# Coco2Composite.net
KiCad netlist of a schematic drawn in EAGLE
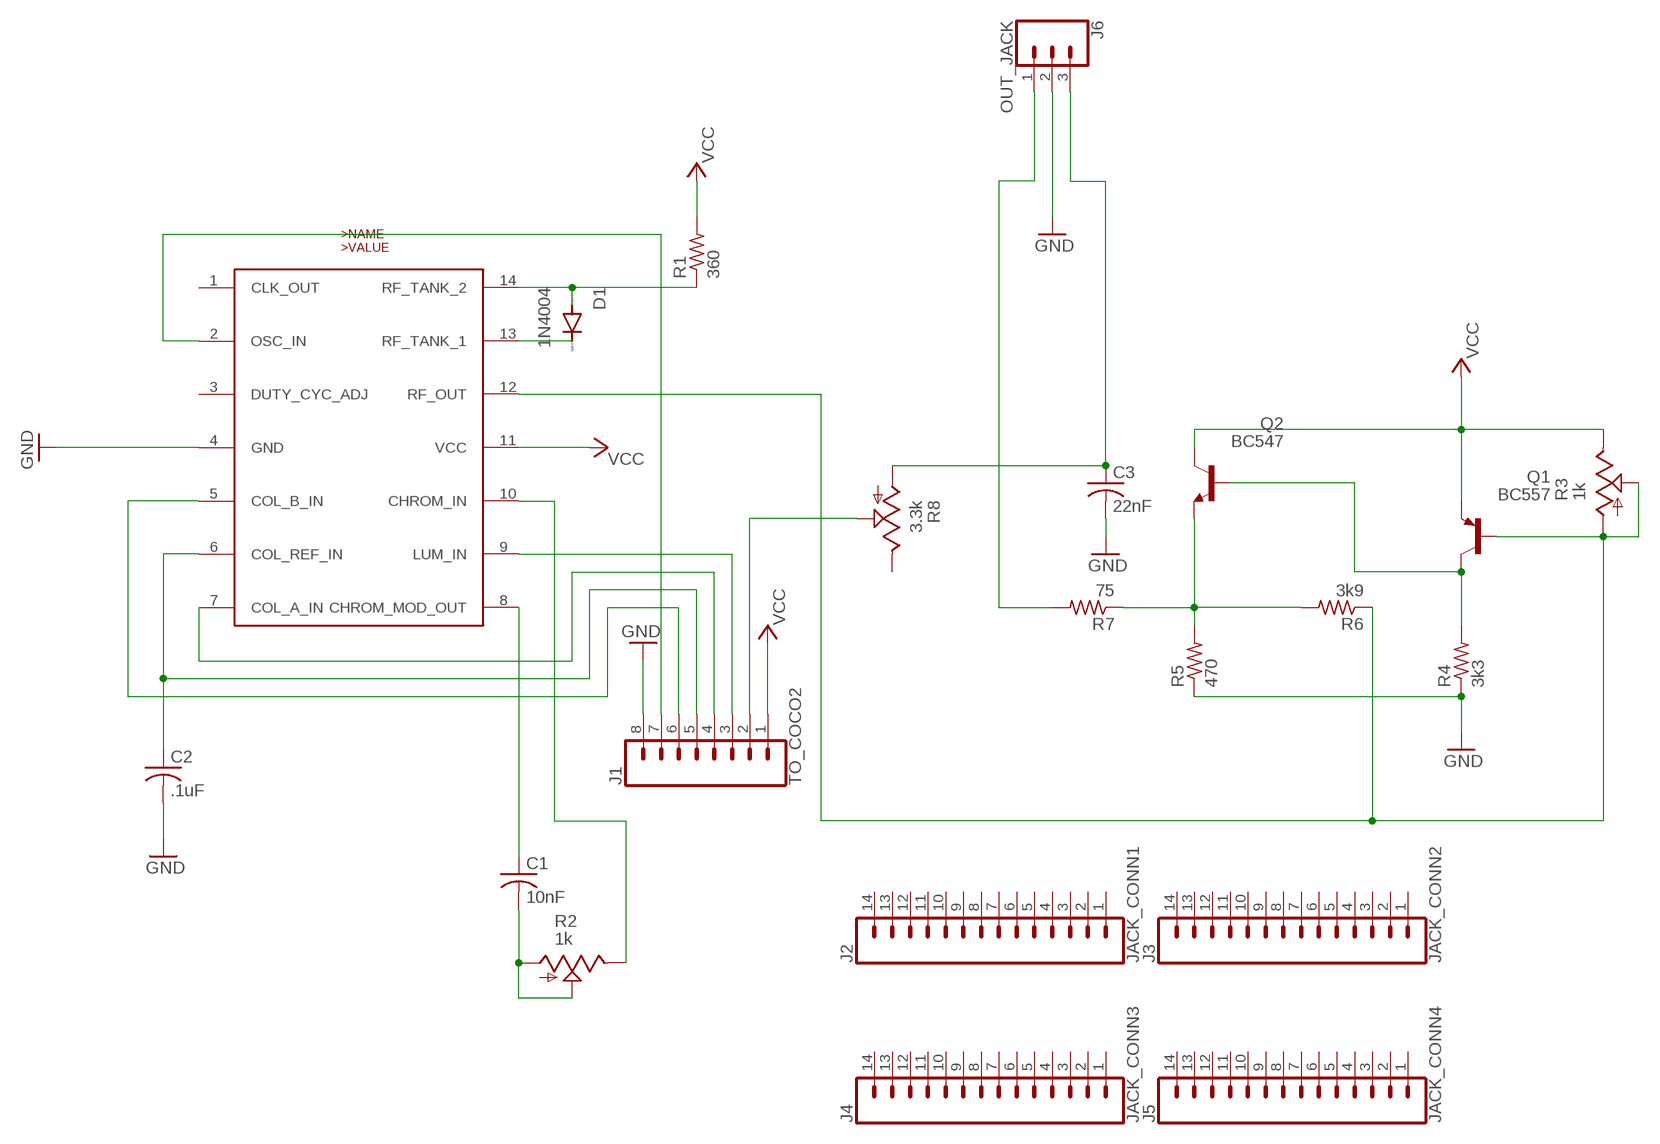
[diagram p0: schematic, sheet 1]

(export (version "E")
  (design (tool "Eeschema 10.0.6"))
  (components
    (comp (ref "C1")
      (value "10nF")
      (footprint "eagle-import:C025-024X044")
      (libsource (lib "eagle-import") (part "C-US025-024X044"))
    )
    (comp (ref "C2")
      (value ".1uF")
      (footprint "eagle-import:C025-024X044")
      (libsource (lib "eagle-import") (part "C-US025-024X044"))
    )
    (comp (ref "C3")
      (value "22nF")
      (footprint "eagle-import:C025-024X044")
      (libsource (lib "eagle-import") (part "C-US025-024X044"))
    )
    (comp (ref "D1")
      (value "1N4004")
      (footprint "eagle-import:DO41-10")
      (libsource (lib "eagle-import") (part "1N4004"))
    )
    (comp (ref "J1")
      (value "TO_COCO2")
      (footprint "eagle-import:1X08")
      (libsource (lib "eagle-import") (part "CONN_08{dblquote}"))
    )
    (comp (ref "J2")
      (value "JACK_CONN1")
      (footprint "eagle-import:1X14")
      (libsource (lib "eagle-import") (part "CONN_14"))
    )
    (comp (ref "J3")
      (value "JACK_CONN2")
      (footprint "eagle-import:1X14")
      (libsource (lib "eagle-import") (part "CONN_14"))
    )
    (comp (ref "J4")
      (value "JACK_CONN3")
      (footprint "eagle-import:1X14")
      (libsource (lib "eagle-import") (part "CONN_14"))
    )
    (comp (ref "J5")
      (value "JACK_CONN4")
      (footprint "eagle-import:1X14")
      (libsource (lib "eagle-import") (part "CONN_14"))
    )
    (comp (ref "J6")
      (value "OUT_JACK")
      (footprint "eagle-import:1X03")
      (libsource (lib "eagle-import") (part "CONN_03"))
    )
    (comp (ref "Q1")
      (value "BC557")
      (footprint "eagle-import:TO92-EBC")
      (libsource (lib "eagle-import") (part "BC557"))
    )
    (comp (ref "Q2")
      (value "BC547")
      (footprint "eagle-import:TO92")
      (libsource (lib "eagle-import") (part "BC547"))
    )
    (comp (ref "R1")
      (value "360")
      (footprint "eagle-import:0204V")
      (libsource (lib "eagle-import") (part "R-US_0204/2V"))
    )
    (comp (ref "R2")
      (value "1k")
      (footprint "eagle-import:B25U")
      (libsource (lib "eagle-import") (part "TRIM_US-B25U"))
    )
    (comp (ref "R3")
      (value "1k")
      (footprint "eagle-import:B25U")
      (libsource (lib "eagle-import") (part "TRIM_US-B25U"))
    )
    (comp (ref "R4")
      (value "3k3")
      (footprint "eagle-import:0204V")
      (libsource (lib "eagle-import") (part "R-US_0204/2V"))
    )
    (comp (ref "R5")
      (value "470")
      (footprint "eagle-import:0204V")
      (libsource (lib "eagle-import") (part "R-US_0204/2V"))
    )
    (comp (ref "R6")
      (value "3k9")
      (footprint "eagle-import:0204V")
      (libsource (lib "eagle-import") (part "R-US_0204/2V"))
    )
    (comp (ref "R7")
      (value "75")
      (footprint "eagle-import:0204V")
      (libsource (lib "eagle-import") (part "R-US_0204/2V"))
    )
    (comp (ref "R8")
      (value "3.3k")
      (footprint "eagle-import:B25U")
      (libsource (lib "eagle-import") (part "TRIM_US-B25U"))
    )
    (comp (ref "U1")
      (value "MC1372")
      (footprint "eagle-import:DIP14")
      (libsource (lib "eagle-import") (part "MC1372"))
    )
  )
  (nets
    (net (code "1") (name "GND") (class "Default")
      (node (ref "C2") (pin "2") (pinfunction "2_2") (pintype "passive"))
      (node (ref "C3") (pin "2") (pinfunction "2_2") (pintype "passive"))
      (node (ref "J1") (pin "8") (pinfunction "8_8") (pintype "passive"))
      (node (ref "J6") (pin "2") (pinfunction "2_2") (pintype "passive"))
      (node (ref "R4") (pin "1") (pinfunction "1_1") (pintype "passive"))
      (node (ref "R5") (pin "1") (pinfunction "1_1") (pintype "passive"))
      (node (ref "U1") (pin "4") (pinfunction "GND_4") (pintype "bidirectional"))
    )
    (net (code "2") (name "Net-(C1-Pad2)") (class "Default")
      (node (ref "C1") (pin "2") (pinfunction "2_2") (pintype "passive"))
      (node (ref "R2") (pin "A") (pinfunction "A_A") (pintype "passive"))
      (node (ref "R2") (pin "S") (pinfunction "S_S") (pintype "passive"))
    )
    (net (code "3") (name "Net-(C3-Pad1)") (class "Default")
      (node (ref "C3") (pin "1") (pinfunction "1_1") (pintype "passive"))
      (node (ref "J6") (pin "3") (pinfunction "3_3") (pintype "passive"))
      (node (ref "R8") (pin "A") (pinfunction "A_A") (pintype "passive"))
    )
    (net (code "4") (name "Net-(J1-Pad2)") (class "Default")
      (node (ref "J1") (pin "2") (pinfunction "2_2") (pintype "passive"))
      (node (ref "R8") (pin "S") (pinfunction "S_S") (pintype "passive"))
    )
    (net (code "5") (name "Net-(J6-Pad1)") (class "Default")
      (node (ref "J6") (pin "1") (pinfunction "1_1") (pintype "passive"))
      (node (ref "R7") (pin "2") (pinfunction "2_2") (pintype "passive"))
    )
    (net (code "6") (name "Net-(Q2-B)") (class "Default")
      (node (ref "Q1") (pin "C") (pinfunction "C_C") (pintype "passive"))
      (node (ref "Q2") (pin "2") (pinfunction "B_2") (pintype "passive"))
      (node (ref "R4") (pin "2") (pinfunction "2_2") (pintype "passive"))
    )
    (net (code "7") (name "Net-(Q2-E)") (class "Default")
      (node (ref "Q2") (pin "1") (pinfunction "E_1") (pintype "passive"))
      (node (ref "R5") (pin "2") (pinfunction "2_2") (pintype "passive"))
      (node (ref "R6") (pin "2") (pinfunction "2_2") (pintype "passive"))
      (node (ref "R7") (pin "1") (pinfunction "1_1") (pintype "passive"))
    )
    (net (code "8") (name "Net-(U1-CHROM_IN)") (class "Default")
      (node (ref "R2") (pin "E") (pinfunction "E_E") (pintype "passive"))
      (node (ref "U1") (pin "10") (pinfunction "CHROM_IN_10") (pintype "bidirectional"))
    )
    (net (code "9") (name "Net-(U1-CHROM_MOD_OUT)") (class "Default")
      (node (ref "C1") (pin "1") (pinfunction "1_1") (pintype "passive"))
      (node (ref "U1") (pin "8") (pinfunction "CHROM_MOD_OUT_8") (pintype "bidirectional"))
    )
    (net (code "10") (name "Net-(U1-COL_A_IN)") (class "Default")
      (node (ref "J1") (pin "4") (pinfunction "4_4") (pintype "passive"))
      (node (ref "U1") (pin "7") (pinfunction "COL_A_IN_7") (pintype "bidirectional"))
    )
    (net (code "11") (name "Net-(U1-COL_B_IN)") (class "Default")
      (node (ref "J1") (pin "6") (pinfunction "6_6") (pintype "passive"))
      (node (ref "U1") (pin "5") (pinfunction "COL_B_IN_5") (pintype "bidirectional"))
    )
    (net (code "12") (name "Net-(U1-COL_REF_IN)") (class "Default")
      (node (ref "C2") (pin "1") (pinfunction "1_1") (pintype "passive"))
      (node (ref "J1") (pin "5") (pinfunction "5_5") (pintype "passive"))
      (node (ref "U1") (pin "6") (pinfunction "COL_REF_IN_6") (pintype "bidirectional"))
    )
    (net (code "13") (name "Net-(U1-LUM_IN)") (class "Default")
      (node (ref "J1") (pin "3") (pinfunction "3_3") (pintype "passive"))
      (node (ref "U1") (pin "9") (pinfunction "LUM_IN_9") (pintype "bidirectional"))
    )
    (net (code "14") (name "Net-(U1-OSC_IN)") (class "Default")
      (node (ref "J1") (pin "7") (pinfunction "7_7") (pintype "passive"))
      (node (ref "U1") (pin "2") (pinfunction "OSC_IN_2") (pintype "bidirectional"))
    )
    (net (code "15") (name "Net-(U1-RF_OUT)") (class "Default")
      (node (ref "Q1") (pin "B") (pinfunction "B_B") (pintype "passive"))
      (node (ref "R3") (pin "A") (pinfunction "A_A") (pintype "passive"))
      (node (ref "R3") (pin "S") (pinfunction "S_S") (pintype "passive"))
      (node (ref "R6") (pin "1") (pinfunction "1_1") (pintype "passive"))
      (node (ref "U1") (pin "12") (pinfunction "RF_OUT_12") (pintype "bidirectional"))
    )
    (net (code "16") (name "Net-(U1-RF_TANK_1)") (class "Default")
      (node (ref "D1") (pin "C") (pinfunction "C_C") (pintype "passive"))
      (node (ref "U1") (pin "13") (pinfunction "RF_TANK_1_13") (pintype "bidirectional"))
    )
    (net (code "17") (name "Net-(U1-RF_TANK_2)") (class "Default")
      (node (ref "D1") (pin "A") (pinfunction "A_A") (pintype "passive"))
      (node (ref "R1") (pin "1") (pinfunction "1_1") (pintype "passive"))
      (node (ref "U1") (pin "14") (pinfunction "RF_TANK_2_14") (pintype "bidirectional"))
    )
    (net (code "18") (name "VCC") (class "Default")
      (node (ref "J1") (pin "1") (pinfunction "1_1") (pintype "passive"))
      (node (ref "Q1") (pin "E") (pinfunction "E_E") (pintype "passive"))
      (node (ref "Q2") (pin "3") (pinfunction "C_3") (pintype "passive"))
      (node (ref "R1") (pin "2") (pinfunction "2_2") (pintype "passive"))
      (node (ref "R3") (pin "E") (pinfunction "E_E") (pintype "passive"))
      (node (ref "U1") (pin "11") (pinfunction "VCC_11") (pintype "bidirectional"))
    )
    (net (code "19") (name "unconnected-(J2-Pad1)") (class "Default")
      (node (ref "J2") (pin "1") (pinfunction "1_1") (pintype "passive"))
    )
    (net (code "20") (name "unconnected-(J2-Pad2)") (class "Default")
      (node (ref "J2") (pin "2") (pinfunction "2_2") (pintype "passive"))
    )
    (net (code "21") (name "unconnected-(J2-Pad3)") (class "Default")
      (node (ref "J2") (pin "3") (pinfunction "3_3") (pintype "passive"))
    )
    (net (code "22") (name "unconnected-(J2-Pad4)") (class "Default")
      (node (ref "J2") (pin "4") (pinfunction "4_4") (pintype "passive"))
    )
    (net (code "23") (name "unconnected-(J2-Pad5)") (class "Default")
      (node (ref "J2") (pin "5") (pinfunction "5_5") (pintype "passive"))
    )
    (net (code "24") (name "unconnected-(J2-Pad6)") (class "Default")
      (node (ref "J2") (pin "6") (pinfunction "6_6") (pintype "passive"))
    )
    (net (code "25") (name "unconnected-(J2-Pad7)") (class "Default")
      (node (ref "J2") (pin "7") (pinfunction "7_7") (pintype "passive"))
    )
    (net (code "26") (name "unconnected-(J2-Pad8)") (class "Default")
      (node (ref "J2") (pin "8") (pinfunction "8_8") (pintype "passive"))
    )
    (net (code "27") (name "unconnected-(J2-Pad9)") (class "Default")
      (node (ref "J2") (pin "9") (pinfunction "9_9") (pintype "passive"))
    )
    (net (code "28") (name "unconnected-(J2-Pad10)") (class "Default")
      (node (ref "J2") (pin "10") (pinfunction "10_10") (pintype "passive"))
    )
    (net (code "29") (name "unconnected-(J2-Pad11)") (class "Default")
      (node (ref "J2") (pin "11") (pinfunction "11_11") (pintype "passive"))
    )
    (net (code "30") (name "unconnected-(J2-Pad12)") (class "Default")
      (node (ref "J2") (pin "12") (pinfunction "12_12") (pintype "passive"))
    )
    (net (code "31") (name "unconnected-(J2-Pad13)") (class "Default")
      (node (ref "J2") (pin "13") (pinfunction "13_13") (pintype "passive"))
    )
    (net (code "32") (name "unconnected-(J2-Pad14)") (class "Default")
      (node (ref "J2") (pin "14") (pinfunction "14_14") (pintype "passive"))
    )
    (net (code "33") (name "unconnected-(J3-Pad1)") (class "Default")
      (node (ref "J3") (pin "1") (pinfunction "1_1") (pintype "passive"))
    )
    (net (code "34") (name "unconnected-(J3-Pad2)") (class "Default")
      (node (ref "J3") (pin "2") (pinfunction "2_2") (pintype "passive"))
    )
    (net (code "35") (name "unconnected-(J3-Pad3)") (class "Default")
      (node (ref "J3") (pin "3") (pinfunction "3_3") (pintype "passive"))
    )
    (net (code "36") (name "unconnected-(J3-Pad4)") (class "Default")
      (node (ref "J3") (pin "4") (pinfunction "4_4") (pintype "passive"))
    )
    (net (code "37") (name "unconnected-(J3-Pad5)") (class "Default")
      (node (ref "J3") (pin "5") (pinfunction "5_5") (pintype "passive"))
    )
    (net (code "38") (name "unconnected-(J3-Pad6)") (class "Default")
      (node (ref "J3") (pin "6") (pinfunction "6_6") (pintype "passive"))
    )
    (net (code "39") (name "unconnected-(J3-Pad7)") (class "Default")
      (node (ref "J3") (pin "7") (pinfunction "7_7") (pintype "passive"))
    )
    (net (code "40") (name "unconnected-(J3-Pad8)") (class "Default")
      (node (ref "J3") (pin "8") (pinfunction "8_8") (pintype "passive"))
    )
    (net (code "41") (name "unconnected-(J3-Pad9)") (class "Default")
      (node (ref "J3") (pin "9") (pinfunction "9_9") (pintype "passive"))
    )
    (net (code "42") (name "unconnected-(J3-Pad10)") (class "Default")
      (node (ref "J3") (pin "10") (pinfunction "10_10") (pintype "passive"))
    )
    (net (code "43") (name "unconnected-(J3-Pad11)") (class "Default")
      (node (ref "J3") (pin "11") (pinfunction "11_11") (pintype "passive"))
    )
    (net (code "44") (name "unconnected-(J3-Pad12)") (class "Default")
      (node (ref "J3") (pin "12") (pinfunction "12_12") (pintype "passive"))
    )
    (net (code "45") (name "unconnected-(J3-Pad13)") (class "Default")
      (node (ref "J3") (pin "13") (pinfunction "13_13") (pintype "passive"))
    )
    (net (code "46") (name "unconnected-(J3-Pad14)") (class "Default")
      (node (ref "J3") (pin "14") (pinfunction "14_14") (pintype "passive"))
    )
    (net (code "47") (name "unconnected-(J4-Pad1)") (class "Default")
      (node (ref "J4") (pin "1") (pinfunction "1_1") (pintype "passive"))
    )
    (net (code "48") (name "unconnected-(J4-Pad2)") (class "Default")
      (node (ref "J4") (pin "2") (pinfunction "2_2") (pintype "passive"))
    )
    (net (code "49") (name "unconnected-(J4-Pad3)") (class "Default")
      (node (ref "J4") (pin "3") (pinfunction "3_3") (pintype "passive"))
    )
    (net (code "50") (name "unconnected-(J4-Pad4)") (class "Default")
      (node (ref "J4") (pin "4") (pinfunction "4_4") (pintype "passive"))
    )
    (net (code "51") (name "unconnected-(J4-Pad5)") (class "Default")
      (node (ref "J4") (pin "5") (pinfunction "5_5") (pintype "passive"))
    )
    (net (code "52") (name "unconnected-(J4-Pad6)") (class "Default")
      (node (ref "J4") (pin "6") (pinfunction "6_6") (pintype "passive"))
    )
    (net (code "53") (name "unconnected-(J4-Pad7)") (class "Default")
      (node (ref "J4") (pin "7") (pinfunction "7_7") (pintype "passive"))
    )
    (net (code "54") (name "unconnected-(J4-Pad8)") (class "Default")
      (node (ref "J4") (pin "8") (pinfunction "8_8") (pintype "passive"))
    )
    (net (code "55") (name "unconnected-(J4-Pad9)") (class "Default")
      (node (ref "J4") (pin "9") (pinfunction "9_9") (pintype "passive"))
    )
    (net (code "56") (name "unconnected-(J4-Pad10)") (class "Default")
      (node (ref "J4") (pin "10") (pinfunction "10_10") (pintype "passive"))
    )
    (net (code "57") (name "unconnected-(J4-Pad11)") (class "Default")
      (node (ref "J4") (pin "11") (pinfunction "11_11") (pintype "passive"))
    )
    (net (code "58") (name "unconnected-(J4-Pad12)") (class "Default")
      (node (ref "J4") (pin "12") (pinfunction "12_12") (pintype "passive"))
    )
    (net (code "59") (name "unconnected-(J4-Pad13)") (class "Default")
      (node (ref "J4") (pin "13") (pinfunction "13_13") (pintype "passive"))
    )
    (net (code "60") (name "unconnected-(J4-Pad14)") (class "Default")
      (node (ref "J4") (pin "14") (pinfunction "14_14") (pintype "passive"))
    )
    (net (code "61") (name "unconnected-(J5-Pad1)") (class "Default")
      (node (ref "J5") (pin "1") (pinfunction "1_1") (pintype "passive"))
    )
    (net (code "62") (name "unconnected-(J5-Pad2)") (class "Default")
      (node (ref "J5") (pin "2") (pinfunction "2_2") (pintype "passive"))
    )
    (net (code "63") (name "unconnected-(J5-Pad3)") (class "Default")
      (node (ref "J5") (pin "3") (pinfunction "3_3") (pintype "passive"))
    )
    (net (code "64") (name "unconnected-(J5-Pad4)") (class "Default")
      (node (ref "J5") (pin "4") (pinfunction "4_4") (pintype "passive"))
    )
    (net (code "65") (name "unconnected-(J5-Pad5)") (class "Default")
      (node (ref "J5") (pin "5") (pinfunction "5_5") (pintype "passive"))
    )
    (net (code "66") (name "unconnected-(J5-Pad6)") (class "Default")
      (node (ref "J5") (pin "6") (pinfunction "6_6") (pintype "passive"))
    )
    (net (code "67") (name "unconnected-(J5-Pad7)") (class "Default")
      (node (ref "J5") (pin "7") (pinfunction "7_7") (pintype "passive"))
    )
    (net (code "68") (name "unconnected-(J5-Pad8)") (class "Default")
      (node (ref "J5") (pin "8") (pinfunction "8_8") (pintype "passive"))
    )
    (net (code "69") (name "unconnected-(J5-Pad9)") (class "Default")
      (node (ref "J5") (pin "9") (pinfunction "9_9") (pintype "passive"))
    )
    (net (code "70") (name "unconnected-(J5-Pad10)") (class "Default")
      (node (ref "J5") (pin "10") (pinfunction "10_10") (pintype "passive"))
    )
    (net (code "71") (name "unconnected-(J5-Pad11)") (class "Default")
      (node (ref "J5") (pin "11") (pinfunction "11_11") (pintype "passive"))
    )
    (net (code "72") (name "unconnected-(J5-Pad12)") (class "Default")
      (node (ref "J5") (pin "12") (pinfunction "12_12") (pintype "passive"))
    )
    (net (code "73") (name "unconnected-(J5-Pad13)") (class "Default")
      (node (ref "J5") (pin "13") (pinfunction "13_13") (pintype "passive"))
    )
    (net (code "74") (name "unconnected-(J5-Pad14)") (class "Default")
      (node (ref "J5") (pin "14") (pinfunction "14_14") (pintype "passive"))
    )
    (net (code "75") (name "unconnected-(R8-PadE)") (class "Default")
      (node (ref "R8") (pin "E") (pinfunction "E_E") (pintype "passive"))
    )
    (net (code "76") (name "unconnected-(U1-CLK_OUT-Pad1)") (class "Default")
      (node (ref "U1") (pin "1") (pinfunction "CLK_OUT_1") (pintype "bidirectional"))
    )
    (net (code "77") (name "unconnected-(U1-DUTY_CYC_ADJ-Pad3)") (class "Default")
      (node (ref "U1") (pin "3") (pinfunction "DUTY_CYC_ADJ_3") (pintype "bidirectional"))
    )
  )
)
